# SCH_Apple_II_Game_port_rev1_0b.net
KiCad netlist of a schematic drawn in EasyEDA
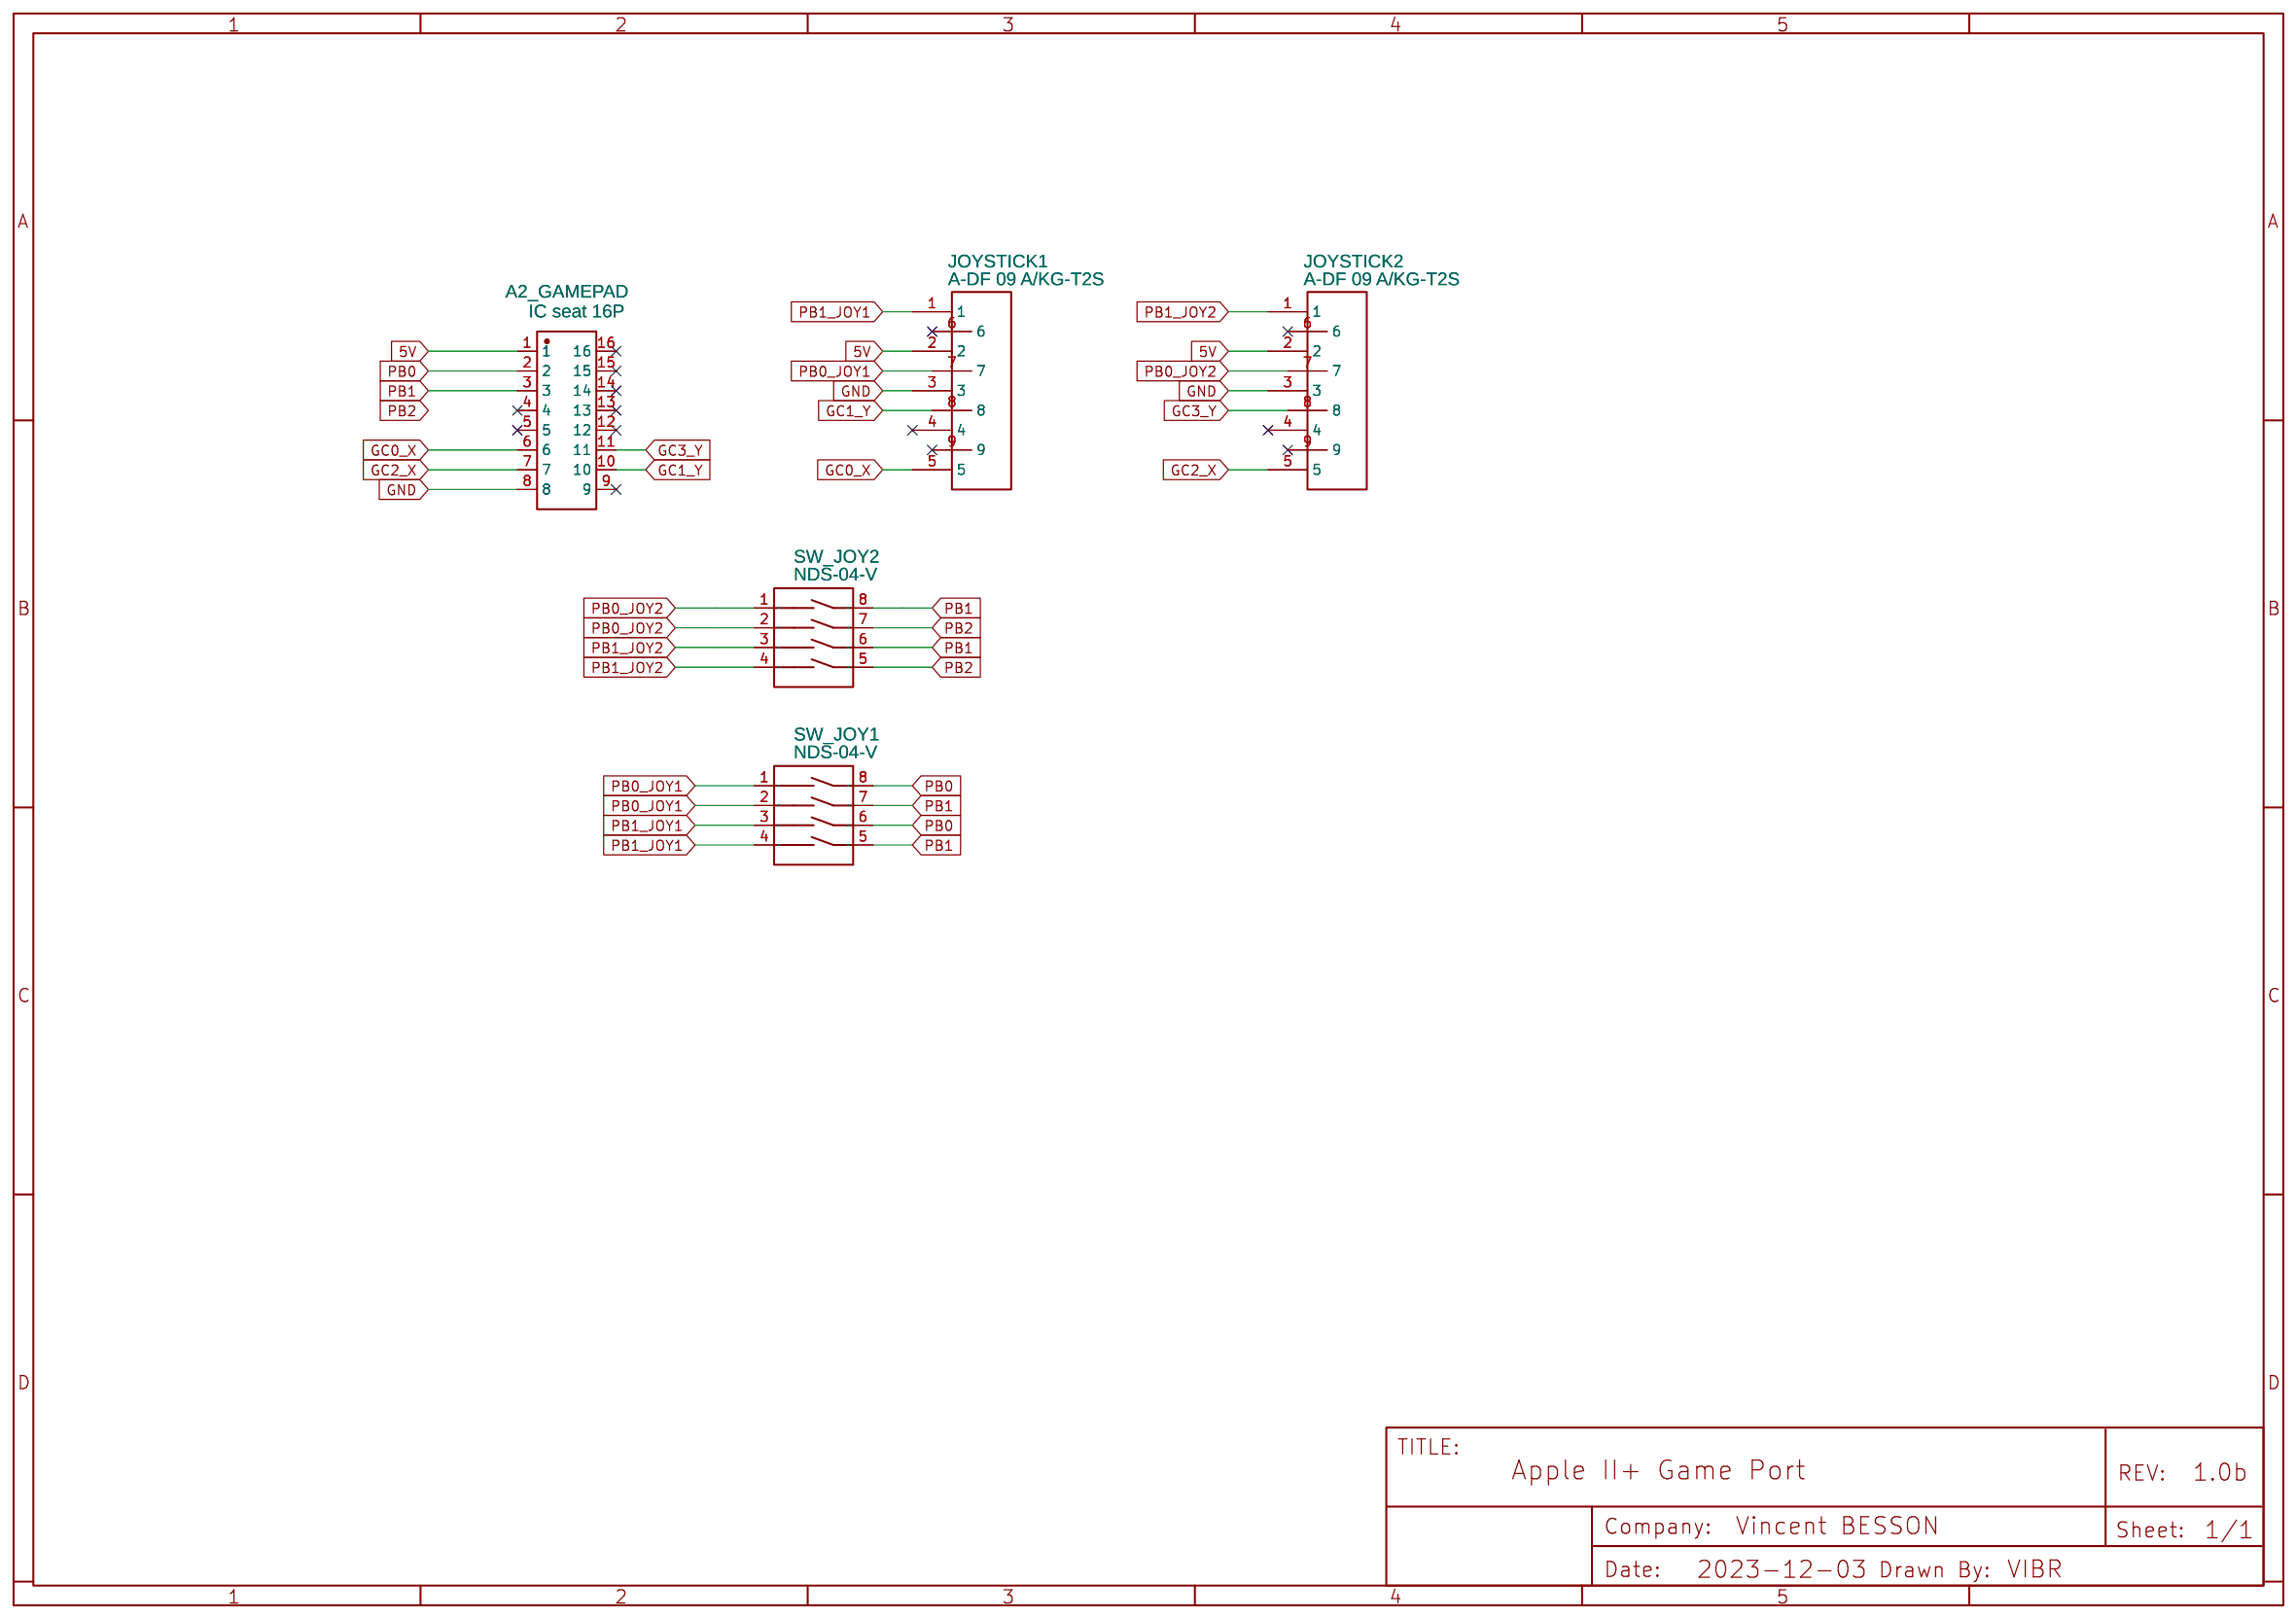
[diagram p0: schematic sheet]

(export (version "E")
  (design (tool "Eeschema 10.0.6"))
  (components
    (comp (ref "A2_GAMEPAD")
      (value "IC seat 16P")
      (fields (field (name "Manufacturer Part") "IC-16P窄") (field (name "Manufacturer") "BOOMELE(博穆精密)"))
      (libsource (lib "") (part "IC seat 16P"))
    )
    (comp (ref "JOYSTICK1") (value "A-DF 09 A/KG-T2S") (libsource (lib "") (part "A-DF 09 A/KG-T2S")))
    (comp (ref "JOYSTICK2") (value "A-DF 09 A/KG-T2S") (libsource (lib "") (part "A-DF 09 A/KG-T2S")))
    (comp (ref "SW_JOY1")
      (value "NDS-04-V")
      (fields (field (name "Manufacturer") "DIP"))
      (libsource (lib "") (part "NDS-04-V"))
    )
    (comp (ref "SW_JOY2")
      (value "NDS-04-V")
      (fields (field (name "Manufacturer") "DIP"))
      (libsource (lib "") (part "NDS-04-V"))
    )
  )
  (nets
    (net (code "1") (name "5V") (class "Default")
      (node (ref "A2_GAMEPAD") (pin "1") (pinfunction "1_1") (pintype "unspecified"))
      (node (ref "JOYSTICK1") (pin "2") (pinfunction "2_2") (pintype "unspecified"))
      (node (ref "JOYSTICK2") (pin "2") (pinfunction "2_2") (pintype "unspecified"))
    )
    (net (code "2") (name "GC0_X") (class "Default")
      (node (ref "A2_GAMEPAD") (pin "6") (pinfunction "6_6") (pintype "unspecified"))
      (node (ref "JOYSTICK1") (pin "5") (pinfunction "5_5") (pintype "unspecified"))
    )
    (net (code "3") (name "GC1_Y") (class "Default")
      (node (ref "A2_GAMEPAD") (pin "10") (pinfunction "10_10") (pintype "unspecified"))
      (node (ref "JOYSTICK1") (pin "8") (pinfunction "8_8") (pintype "unspecified"))
    )
    (net (code "4") (name "GC2_X") (class "Default")
      (node (ref "A2_GAMEPAD") (pin "7") (pinfunction "7_7") (pintype "unspecified"))
      (node (ref "JOYSTICK2") (pin "5") (pinfunction "5_5") (pintype "unspecified"))
    )
    (net (code "5") (name "GC3_Y") (class "Default")
      (node (ref "A2_GAMEPAD") (pin "11") (pinfunction "11_11") (pintype "unspecified"))
      (node (ref "JOYSTICK2") (pin "8") (pinfunction "8_8") (pintype "unspecified"))
    )
    (net (code "6") (name "GND") (class "Default")
      (node (ref "A2_GAMEPAD") (pin "8") (pinfunction "8_8") (pintype "unspecified"))
      (node (ref "JOYSTICK1") (pin "3") (pinfunction "3_3") (pintype "unspecified"))
      (node (ref "JOYSTICK2") (pin "3") (pinfunction "3_3") (pintype "unspecified"))
    )
    (net (code "7") (name "PB0") (class "Default")
      (node (ref "A2_GAMEPAD") (pin "2") (pinfunction "2_2") (pintype "unspecified"))
      (node (ref "SW_JOY1") (pin "6") (pinfunction "6_6") (pintype "unspecified"))
      (node (ref "SW_JOY1") (pin "8") (pinfunction "8_8") (pintype "unspecified"))
    )
    (net (code "8") (name "PB0_JOY1") (class "Default")
      (node (ref "JOYSTICK1") (pin "7") (pinfunction "7_7") (pintype "unspecified"))
      (node (ref "SW_JOY1") (pin "1") (pinfunction "1_1") (pintype "unspecified"))
      (node (ref "SW_JOY1") (pin "2") (pinfunction "2_2") (pintype "unspecified"))
    )
    (net (code "9") (name "PB0_JOY2") (class "Default")
      (node (ref "JOYSTICK2") (pin "7") (pinfunction "7_7") (pintype "unspecified"))
      (node (ref "SW_JOY2") (pin "1") (pinfunction "1_1") (pintype "unspecified"))
      (node (ref "SW_JOY2") (pin "2") (pinfunction "2_2") (pintype "unspecified"))
    )
    (net (code "10") (name "PB1") (class "Default")
      (node (ref "A2_GAMEPAD") (pin "3") (pinfunction "3_3") (pintype "unspecified"))
      (node (ref "SW_JOY1") (pin "5") (pinfunction "5_5") (pintype "unspecified"))
      (node (ref "SW_JOY1") (pin "7") (pinfunction "7_7") (pintype "unspecified"))
      (node (ref "SW_JOY2") (pin "6") (pinfunction "6_6") (pintype "unspecified"))
      (node (ref "SW_JOY2") (pin "8") (pinfunction "8_8") (pintype "unspecified"))
    )
    (net (code "11") (name "PB1_JOY1") (class "Default")
      (node (ref "JOYSTICK1") (pin "1") (pinfunction "1_1") (pintype "unspecified"))
      (node (ref "SW_JOY1") (pin "3") (pinfunction "3_3") (pintype "unspecified"))
      (node (ref "SW_JOY1") (pin "4") (pinfunction "4_4") (pintype "unspecified"))
    )
    (net (code "12") (name "PB1_JOY2") (class "Default")
      (node (ref "JOYSTICK2") (pin "1") (pinfunction "1_1") (pintype "unspecified"))
      (node (ref "SW_JOY2") (pin "3") (pinfunction "3_3") (pintype "unspecified"))
      (node (ref "SW_JOY2") (pin "4") (pinfunction "4_4") (pintype "unspecified"))
    )
    (net (code "13") (name "PB2") (class "Default")
      (node (ref "SW_JOY2") (pin "5") (pinfunction "5_5") (pintype "unspecified"))
      (node (ref "SW_JOY2") (pin "7") (pinfunction "7_7") (pintype "unspecified"))
    )
    (net (code "14") (name "unconnected-(A2_GAMEPAD-Pad4)") (class "Default")
      (node (ref "A2_GAMEPAD") (pin "4") (pinfunction "4_4") (pintype "unspecified+no_connect"))
    )
    (net (code "15") (name "unconnected-(A2_GAMEPAD-Pad5)") (class "Default")
      (node (ref "A2_GAMEPAD") (pin "5") (pinfunction "5_5") (pintype "unspecified+no_connect"))
    )
    (net (code "16") (name "unconnected-(A2_GAMEPAD-Pad9)") (class "Default")
      (node (ref "A2_GAMEPAD") (pin "9") (pinfunction "9_9") (pintype "unspecified+no_connect"))
    )
    (net (code "17") (name "unconnected-(A2_GAMEPAD-Pad12)") (class "Default")
      (node (ref "A2_GAMEPAD") (pin "12") (pinfunction "12_12") (pintype "unspecified+no_connect"))
    )
    (net (code "18") (name "unconnected-(A2_GAMEPAD-Pad13)") (class "Default")
      (node (ref "A2_GAMEPAD") (pin "13") (pinfunction "13_13") (pintype "unspecified+no_connect"))
    )
    (net (code "19") (name "unconnected-(A2_GAMEPAD-Pad14)") (class "Default")
      (node (ref "A2_GAMEPAD") (pin "14") (pinfunction "14_14") (pintype "unspecified+no_connect"))
    )
    (net (code "20") (name "unconnected-(A2_GAMEPAD-Pad15)") (class "Default")
      (node (ref "A2_GAMEPAD") (pin "15") (pinfunction "15_15") (pintype "unspecified+no_connect"))
    )
    (net (code "21") (name "unconnected-(A2_GAMEPAD-Pad16)") (class "Default")
      (node (ref "A2_GAMEPAD") (pin "16") (pinfunction "16_16") (pintype "unspecified+no_connect"))
    )
    (net (code "22") (name "unconnected-(JOYSTICK1-Pad4)") (class "Default")
      (node (ref "JOYSTICK1") (pin "4") (pinfunction "4_4") (pintype "unspecified+no_connect"))
    )
    (net (code "23") (name "unconnected-(JOYSTICK1-Pad6)") (class "Default")
      (node (ref "JOYSTICK1") (pin "6") (pinfunction "6_6") (pintype "unspecified+no_connect"))
    )
    (net (code "24") (name "unconnected-(JOYSTICK1-Pad9)") (class "Default")
      (node (ref "JOYSTICK1") (pin "9") (pinfunction "9_9") (pintype "unspecified+no_connect"))
    )
    (net (code "25") (name "unconnected-(JOYSTICK2-Pad4)") (class "Default")
      (node (ref "JOYSTICK2") (pin "4") (pinfunction "4_4") (pintype "unspecified+no_connect"))
    )
    (net (code "26") (name "unconnected-(JOYSTICK2-Pad6)") (class "Default")
      (node (ref "JOYSTICK2") (pin "6") (pinfunction "6_6") (pintype "unspecified+no_connect"))
    )
    (net (code "27") (name "unconnected-(JOYSTICK2-Pad9)") (class "Default")
      (node (ref "JOYSTICK2") (pin "9") (pinfunction "9_9") (pintype "unspecified+no_connect"))
    )
  )
)
